# 5V.net
KiCad netlist of a schematic drawn in Altium Designer
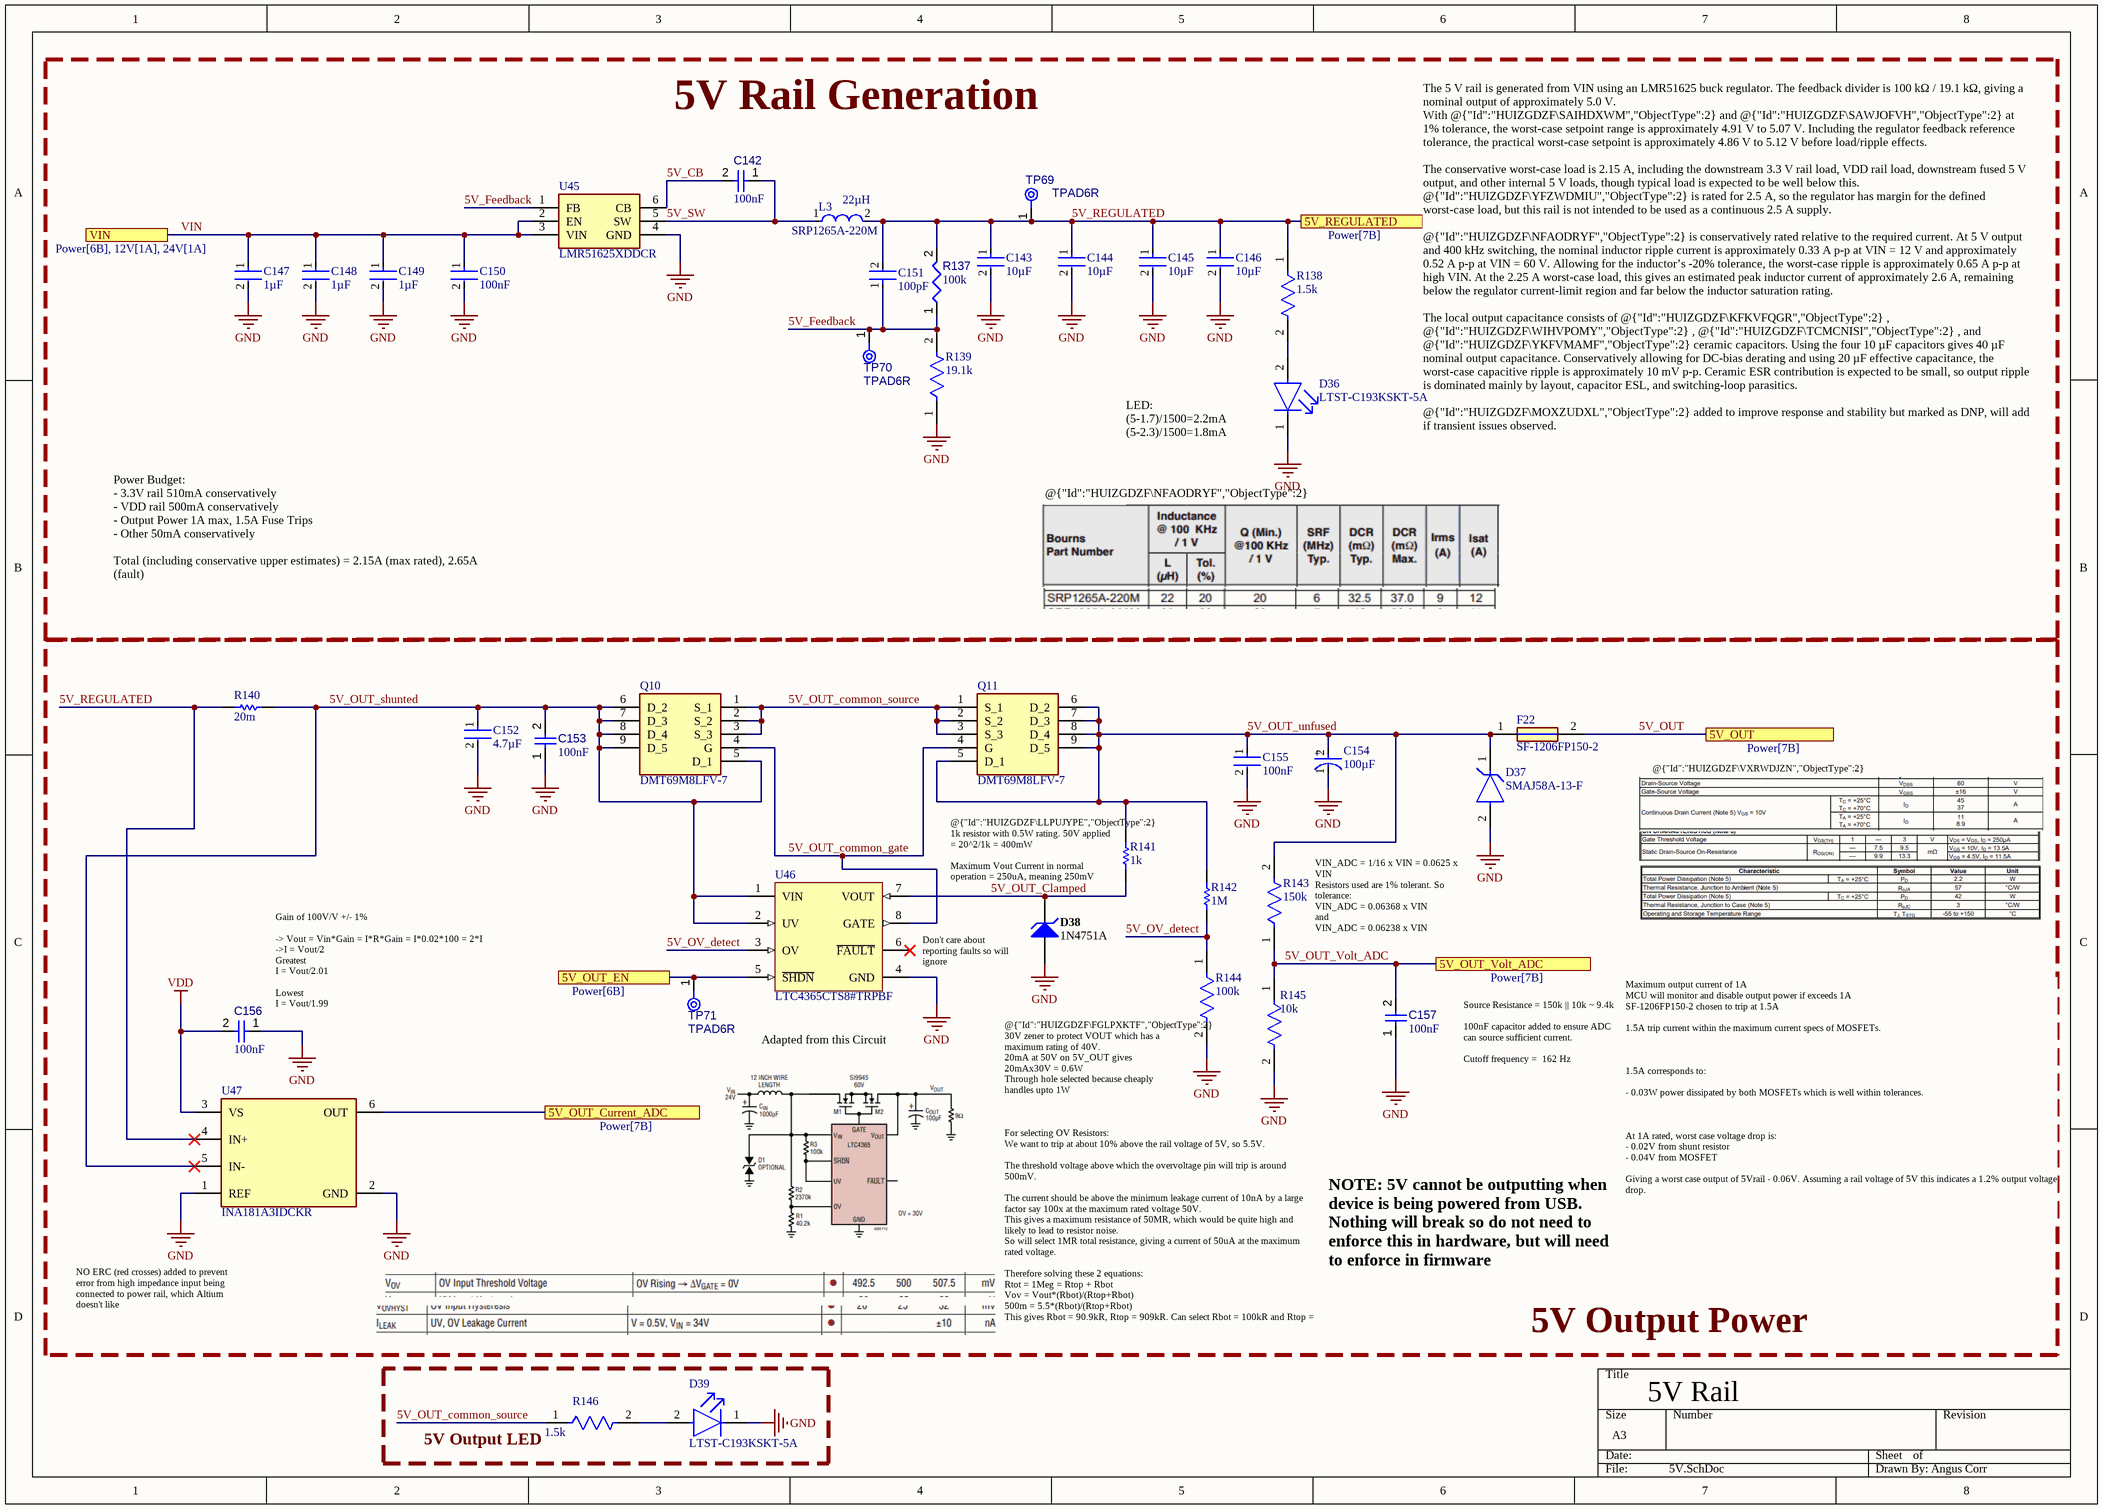
[diagram p0:  5V.SchDoc]

(export (version "E")
  (design (tool "Eeschema 10.0.6"))
  (components
    (comp (ref "C142")
      (value "100nF")
      (footprint "CAPC1608X90X40NL10T20")
      (description "Chip Capacitor, 100 nF, +/- 10%, 50 V, 0603 (1608 Metric)")
      (fields (field (name "TOLERANCE") "10%") (field (name "Comment") "Capacitor 100 nF +/-10% 50 V 0603"))
      (libsource (lib "HIL RIG FYP") (part "CAP-NP-2"))
    )
    (comp (ref "C143")
      (value "10µF")
      (footprint "FP-GRM31C-0_2-e0_3_0_8-IPC_C")
      (description "25V 10uF X7R ±10% 1206 Multilayer Ceramic Capacitors MLCC - SMD/SMT ROHS")
      (fields (field (name "TOLERANCE") "10%") (field (name "VOLTAGE") "25V"))
      (libsource (lib "HIL RIG FYP") (part "02cd4be3c70576c341d710602a673aa"))
    )
    (comp (ref "C144")
      (value "10µF")
      (footprint "FP-GRM31C-0_2-e0_3_0_8-IPC_C")
      (description "25V 10uF X7R ±10% 1206 Multilayer Ceramic Capacitors MLCC - SMD/SMT ROHS")
      (fields (field (name "TOLERANCE") "10%") (field (name "VOLTAGE") "25V"))
      (libsource (lib "HIL RIG FYP") (part "02cd4be3c70576c341d710602a673aa"))
    )
    (comp (ref "C145")
      (value "10µF")
      (footprint "FP-GRM31C-0_2-e0_3_0_8-IPC_C")
      (description "25V 10uF X7R ±10% 1206 Multilayer Ceramic Capacitors MLCC - SMD/SMT ROHS")
      (fields (field (name "TOLERANCE") "10%") (field (name "VOLTAGE") "25V"))
      (libsource (lib "HIL RIG FYP") (part "02cd4be3c70576c341d710602a673aa"))
    )
    (comp (ref "C146")
      (value "10µF")
      (footprint "FP-GRM31C-0_2-e0_3_0_8-IPC_C")
      (description "25V 10uF X7R ±10% 1206 Multilayer Ceramic Capacitors MLCC - SMD/SMT ROHS")
      (fields (field (name "TOLERANCE") "10%") (field (name "VOLTAGE") "25V"))
      (libsource (lib "HIL RIG FYP") (part "02cd4be3c70576c341d710602a673aa"))
    )
    (comp (ref "C147")
      (value "1µF")
      (footprint "FP-GRJ21B-0_35-MFG")
      (description "100V 1uF X7S ±10% 0805 Multilayer Ceramic Capacitors MLCC - SMD/SMT ROHS")
      (fields (field (name "TOLERANCE") "10%") (field (name "Comment") "GRJ21BC72A105KE11L"))
      (libsource (lib "HIL RIG FYP") (part "b4654b650e69147ec39a6b967a45e02"))
    )
    (comp (ref "C148")
      (value "1µF")
      (footprint "FP-GRJ21B-0_35-MFG")
      (description "100V 1uF X7S ±10% 0805 Multilayer Ceramic Capacitors MLCC - SMD/SMT ROHS")
      (fields (field (name "TOLERANCE") "10%") (field (name "Comment") "GRJ21BC72A105KE11L"))
      (libsource (lib "HIL RIG FYP") (part "b4654b650e69147ec39a6b967a45e02"))
    )
    (comp (ref "C149")
      (value "1µF")
      (footprint "FP-GRJ21B-0_35-MFG")
      (description "100V 1uF X7S ±10% 0805 Multilayer Ceramic Capacitors MLCC - SMD/SMT ROHS")
      (fields (field (name "TOLERANCE") "10%") (field (name "Comment") "GRJ21BC72A105KE11L"))
      (libsource (lib "HIL RIG FYP") (part "b4654b650e69147ec39a6b967a45e02"))
    )
    (comp (ref "C150")
      (value "100nF")
      (footprint "FP-GRM31C-0_2-e0_3_0_8-IPC_C")
      (description "100V 100nF C0G ±5% 1206 Multilayer Ceramic Capacitors MLCC - SMD/SMT ROHS")
      (fields (field (name "TOLERANCE") "5%") (field (name "Comment") "GRM31C5C2A104JA01L"))
      (libsource (lib "HIL RIG FYP") (part "02cd4be3c70576c341d710602a673aa"))
    )
    (comp (ref "C151")
      (value "100pF")
      (footprint "FP-C0603C-CF-IPC_B")
      (description "Multilayer Ceramic Capacitors MLCC - SMD/SMT 50V 100pF X8R 0603 1%")
      (fields (field (name "Comment") "C0603C101F5HACTU"))
      (libsource (lib "HIL RIG FYP") (part "b4654b650e69147ec39a6b967a45e02"))
    )
    (comp (ref "C152")
      (value "4.7µF")
      (footprint "FP-GRM21B-0_2-e0_2_0_7-MFG")
      (description "50V 4.7uF X7R ±10% 0805 Multilayer Ceramic Capacitors MLCC - SMD/SMT ROHS")
      (fields (field (name "TOLERANCE") "10%") (field (name "Comment") "GRM21BZ71H475KE15L"))
      (libsource (lib "HIL RIG FYP") (part "b4654b650e69147ec39a6b967a45e02"))
    )
    (comp (ref "C153")
      (value "100nF")
      (footprint "CAPC1608X90X40NL10T20")
      (description "Chip Capacitor, 100 nF, +/- 10%, 50 V, 0603 (1608 Metric)")
      (fields (field (name "TOLERANCE") "10%") (field (name "Comment") "Capacitor 100 nF +/-10% 50 V 0603"))
      (libsource (lib "HIL RIG FYP") (part "CAP-NP-2"))
    )
    (comp (ref "C154")
      (value "100µF")
      (footprint "FP-MVYAKE0-MFG")
      (description "Cap Aluminum 100uF 100V 20% (12.5 X 13.5mm) SMD 450mA 5000h 105°C T/R")
      (fields (field (name "TOLERANCE") "20%") (field (name "Comment") "EMVY101ARA101MKE0S"))
      (libsource (lib "HIL RIG FYP") (part "203bc49f2ac43e59fd269a8c329ed05"))
    )
    (comp (ref "C155")
      (value "100nF")
      (footprint "FP-GRM31C-0_2-e0_3_0_8-IPC_C")
      (description "100V 100nF C0G ±5% 1206 Multilayer Ceramic Capacitors MLCC - SMD/SMT ROHS")
      (fields (field (name "TOLERANCE") "5%") (field (name "Comment") "GRM31C5C2A104JA01L"))
      (libsource (lib "HIL RIG FYP") (part "02cd4be3c70576c341d710602a673aa"))
    )
    (comp (ref "C156")
      (value "100nF")
      (footprint "CAPC1608X90X40NL10T20")
      (description "Chip Capacitor, 100 nF, +/- 10%, 50 V, 0603 (1608 Metric)")
      (fields (field (name "TOLERANCE") "10%") (field (name "Comment") "Capacitor 100 nF +/-10% 50 V 0603"))
      (libsource (lib "HIL RIG FYP") (part "CAP-NP-2"))
    )
    (comp (ref "C157")
      (value "100nF")
      (footprint "CAPC1608X90X40NL10T20")
      (description "Chip Capacitor, 100 nF, +/- 10%, 50 V, 0603 (1608 Metric)")
      (fields (field (name "TOLERANCE") "10%") (field (name "Comment") "Capacitor 100 nF +/-10% 50 V 0603"))
      (libsource (lib "HIL RIG FYP") (part "CAP-NP-2"))
    )
    (comp (ref "D36")
      (value "LTST-C193KSKT-5A")
      (footprint "FP-LTST-C193KGKT-5A-MFG")
      (description "LED yellow 0603 wavelength 587~594.5nm light intensity 7.1~45mcd Front Mounting")
      (libsource (lib "HIL RIG FYP") (part "8706943c75ba83719d021d2fdc84c58"))
    )
    (comp (ref "D37")
      (value "SMAJ58A-13-F")
      (footprint "FP-SMA-MFG")
      (description "SMAJ Series 58 V 400 W SMT Uni-Directional TVS Diode - DO-214AC")
      (libsource (lib "HIL RIG FYP") (part "f813f71cba58e380607f5dd3caf9714"))
    )
    (comp (ref "D38")
      (value "1N4751A")
      (footprint "FAIR-DO-41-2_V")
      (description "1N4751 Series 1 W 30 V 5 uA Axial Through Hole Zener Diode - DO-41")
      (libsource (lib "HIL RIG FYP") (part "FAIR-DZEN-A1K2-2"))
    )
    (comp (ref "D39")
      (value "LTST-C193KSKT-5A")
      (footprint "FP-LTST-C193KGKT-5A-MFG")
      (description "LED yellow 0603 wavelength 587~594.5nm light intensity 7.1~45mcd Front Mounting")
      (libsource (lib "HIL RIG FYP") (part "8706943c75ba83719d021d2fdc84c58"))
    )
    (comp (ref "F22")
      (value "SF-1206FP150-2")
      (footprint "FUSC3116X70N")
      (description "Surface Mount Fuses 1.5A Fast Acting 1206 Singlfuse")
      (fields (field (name "MOUSER PART NUMBER") "652-SF-1206FP150-2"))
      (libsource (lib "HIL RIG FYP") (part "SF-1206FP150-2"))
    )
    (comp (ref "L3")
      (value "SRP1265A-220M")
      (footprint "FP-SRP1265A-MFG")
      (fields (field (name "TOLERANCE") "20%") (field (name "ALTIUM_VALUE") "22µH"))
      (libsource (lib "HIL RIG FYP") (part "725321dda6339637d4d059423bc1c3c"))
    )
    (comp (ref "Q10")
      (value "DMT69M8LFV-7")
      (footprint "DMP3036SFV7")
      (description "MOSFET MOSFET BVDSS: 41V-60V")
      (fields (field (name "MOUSER PART NUMBER") "621-DMT69M8LFV-7"))
      (libsource (lib "") (part "DMT69M8LFV-7_1"))
    )
    (comp (ref "Q11")
      (value "DMT69M8LFV-7")
      (footprint "DMP3036SFV7")
      (description "MOSFET MOSFET BVDSS: 41V-60V")
      (fields (field (name "MOUSER PART NUMBER") "621-DMT69M8LFV-7"))
      (libsource (lib "HIL RIG FYP") (part "DMT69M8LFV-7"))
    )
    (comp (ref "R137")
      (value "100k")
      (footprint "FP-AC0603-IPC_C")
      (description "Res Thick Film 0603 100K Ohm 1% 0.1W(1/10W) ±100ppm/C Pad SMD T/R Automotive")
      (fields (field (name "TOLERANCE") "1%") (field (name "Comment") "AC0603FR-07100KL"))
      (libsource (lib "HIL RIG FYP") (part "RES-2"))
    )
    (comp (ref "R138")
      (value "1.5k")
      (footprint "FP-RT0603-IPC_C")
      (description "Res Thin Film 0603 1.5K Ohm 0.1% 1/10W ±25ppm/°C Molded SMD SMD Paper T/R")
      (fields (field (name "TOLERANCE") "0.1%") (field (name "Comment") "RT0603BRD071K5L"))
      (libsource (lib "HIL RIG FYP") (part "1029c3af85768c4190bb7ad29bc67b5"))
    )
    (comp (ref "R139")
      (value "19.1k")
      (footprint "FP-RT0603-IPC_C")
      (description "100mW Thin Film Resistor ±25ppm/℃ ±0.1% 19.1kΩ 0603 Chip Resistor - Surface Mount ROHS")
      (fields (field (name "TOLERANCE") "0.1%") (field (name "Comment") "RT0603BRD0719K1L"))
      (libsource (lib "HIL RIG FYP") (part "1029c3af85768c4190bb7ad29bc67b5"))
    )
    (comp (ref "R140")
      (value "20m")
      (footprint "RESC3216X89X51NL25T25")
      (description "Res Metal Strip 1206 0.02 Ohm 1% 1/4W ±75ppm/°C Molded SMD SMD Embossed Plastic T/R")
      (fields (field (name "TOLERANCE") "1%") (field (name "Comment") "WSL1206R0200FEA"))
      (libsource (lib "HIL RIG FYP") (part "RES"))
    )
    (comp (ref "R141")
      (value "1k")
      (footprint "RESC3126X60X50ML10T20")
      (description "500mW Thick Film Resistors 200V ±100ppm/℃ ±1% 1kΩ 1210 Chip Resistor - Surface Mount ROHS")
      (fields (field (name "TOLERANCE") "1%") (field (name "Comment") "AC1210FR-071KL"))
      (libsource (lib "HIL RIG FYP") (part "RES"))
    )
    (comp (ref "R142")
      (value "1M")
      (footprint "RESC2013X60X35ML10T20")
      (fields (field (name "TOLERANCE") "0.1%") (field (name "Comment") "RT0805BRD071ML"))
      (libsource (lib "HIL RIG FYP") (part "RES"))
    )
    (comp (ref "R143")
      (value "150k")
      (footprint "FP-CRGCQ0603-IPC_A")
      (description "Res Thick Film 0603 150K Ohm 1% 0.1W(1/10W) ±100ppm/C Pad SMD Automotive T/R")
      (fields (field (name "TOLERANCE") "1%") (field (name "Comment") "CRGCQ0603F150K"))
      (libsource (lib "HIL RIG FYP") (part "1029c3af85768c4190bb7ad29bc67b5"))
    )
    (comp (ref "R144")
      (value "100k")
      (footprint "FP-RT0603-IPC_C")
      (description "100mW Thin Film Resistor 75V ±50ppm/℃ ±0.1% 100kΩ 0603 Chip Resistor - Surface Mount ROHS")
      (fields (field (name "TOLERANCE") "0.1%") (field (name "Comment") "RT0603BRE07100KL"))
      (libsource (lib "HIL RIG FYP") (part "1029c3af85768c4190bb7ad29bc67b5"))
    )
    (comp (ref "R145")
      (value "10k")
      (footprint "FP-RT0603-IPC_C")
      (description "Res Thin Film 0603 10K Ohm 0.1% 1/10W ¦25ppm/¦C SMD Paper T/R")
      (fields (field (name "TOLERANCE") "0.1%") (field (name "Comment") "RT0603BRD0710KL"))
      (libsource (lib "HIL RIG FYP") (part "1029c3af85768c4190bb7ad29bc67b5"))
    )
    (comp (ref "R146")
      (value "1.5k")
      (footprint "FP-RT0603-IPC_C")
      (description "Res Thin Film 0603 1.5K Ohm 0.1% 1/10W ±25ppm/°C Molded SMD SMD Paper T/R")
      (fields (field (name "TOLERANCE") "0.1%") (field (name "Comment") "RT0603BRD071K5L"))
      (libsource (lib "HIL RIG FYP") (part "1029c3af85768c4190bb7ad29bc67b5"))
    )
    (comp (ref "TP69")
      (value "TPAD6R")
      (footprint "TP06R")
      (description "0.6mm round")
      (libsource (lib "HIL RIG FYP") (part "CMP-001-0001-4"))
    )
    (comp (ref "TP70")
      (value "TPAD6R")
      (footprint "TP06R")
      (description "0.6mm round")
      (libsource (lib "HIL RIG FYP") (part "CMP-001-0001-4"))
    )
    (comp (ref "TP71")
      (value "TPAD6R")
      (footprint "TP06R")
      (description "0.6mm round")
      (libsource (lib "HIL RIG FYP") (part "CMP-001-0001-4"))
    )
    (comp (ref "U45")
      (value "LMR51625XDDCR")
      (footprint "SOT95P280X110-6N")
      (description "Switching Voltage Regulators SIMPLE SWITCHER synchronous buck converter with 4.3V-to-60V")
      (fields (field (name "MOUSER PART NUMBER") "595-LMR51625XDDCR"))
      (libsource (lib "HIL RIG FYP") (part "LMR51625XDDCR"))
    )
    (comp (ref "U46")
      (value "LTC4365CTS8#TRPBF")
      (footprint "LT-TS8-8-TSOT-23_V")
      (description "Overvoltage, Undervoltage and Reverse Supply Protection Controller")
      (libsource (lib "HIL RIG FYP") (part "LT-LTC4365-TS8-8"))
    )
    (comp (ref "U47")
      (value "INA181A3IDCKR")
      (footprint "FP-DCK0006A-IPC_A")
      (description "26-V bi-directional 350-kHz current-sense amplifier 6-SC70 -40 to 125")
      (libsource (lib "HIL RIG FYP") (part "a7b5cee9b6bc60f4871af0ee2c3b109"))
    )
  )
  (nets
    (net (code "1") (name "/5V_CB") (class "Default")
      (node (ref "C142") (pin "2") (pinfunction "2_2") (pintype "passive"))
      (node (ref "U45") (pin "6") (pinfunction "CB_6") (pintype "passive"))
    )
    (net (code "2") (name "/5V_Feedback") (class "Default")
      (node (ref "C151") (pin "1") (pinfunction "1_1") (pintype "passive"))
      (node (ref "R137") (pin "1") (pinfunction "1_1") (pintype "passive"))
      (node (ref "R139") (pin "2") (pinfunction "2_2") (pintype "passive"))
      (node (ref "TP70") (pin "1") (pinfunction "TP_1") (pintype "passive"))
      (node (ref "U45") (pin "1") (pinfunction "FB_1") (pintype "passive"))
    )
    (net (code "3") (name "/5V_OUT") (class "Default")
      (node (ref "F22") (pin "2") (pinfunction "2_2") (pintype "passive"))
    )
    (net (code "4") (name "/5V_OUT_Clamped") (class "Default")
      (node (ref "D38") (pin "2") (pinfunction "K_2") (pintype "passive"))
      (node (ref "R141") (pin "1") (pinfunction "1_1") (pintype "passive"))
      (node (ref "U46") (pin "7") (pinfunction "VOUT_7") (pintype "input"))
    )
    (net (code "5") (name "/5V_OUT_Current_ADC") (class "Default")
      (node (ref "U47") (pin "6") (pinfunction "OUT_6") (pintype "passive"))
    )
    (net (code "6") (name "/5V_OUT_EN") (class "Default")
      (node (ref "TP71") (pin "1") (pinfunction "TP_1") (pintype "passive"))
      (node (ref "U46") (pin "5") (pinfunction "~{SHDN}_5") (pintype "input"))
    )
    (net (code "7") (name "/5V_OUT_Volt_ADC") (class "Default")
      (node (ref "C157") (pin "2") (pinfunction "2_2") (pintype "passive"))
      (node (ref "R143") (pin "1") (pinfunction "1_1") (pintype "passive"))
      (node (ref "R145") (pin "1") (pinfunction "1_1") (pintype "passive"))
    )
    (net (code "8") (name "/5V_OUT_common_gate") (class "Default")
      (node (ref "Q10") (pin "4") (pinfunction "G_4") (pintype "passive"))
      (node (ref "Q11") (pin "4") (pinfunction "G_4") (pintype "passive"))
      (node (ref "U46") (pin "8") (pinfunction "GATE_8") (pintype "output"))
    )
    (net (code "9") (name "/5V_OUT_common_source") (class "Default")
      (node (ref "Q10") (pin "1") (pinfunction "S_1_1") (pintype "passive"))
      (node (ref "Q10") (pin "2") (pinfunction "S_2_2") (pintype "passive"))
      (node (ref "Q10") (pin "3") (pinfunction "S_3_3") (pintype "passive"))
      (node (ref "Q11") (pin "1") (pinfunction "S_1_1") (pintype "passive"))
      (node (ref "Q11") (pin "2") (pinfunction "S_2_2") (pintype "passive"))
      (node (ref "Q11") (pin "3") (pinfunction "S_3_3") (pintype "passive"))
      (node (ref "R146") (pin "1") (pinfunction "1_1") (pintype "passive"))
    )
    (net (code "10") (name "/5V_OUT_shunted") (class "Default")
      (node (ref "C152") (pin "1") (pinfunction "1_1") (pintype "passive"))
      (node (ref "C153") (pin "2") (pinfunction "2_2") (pintype "passive"))
      (node (ref "Q10") (pin "5") (pinfunction "D_1_5") (pintype "passive"))
      (node (ref "Q10") (pin "6") (pinfunction "D_2_6") (pintype "passive"))
      (node (ref "Q10") (pin "7") (pinfunction "D_3_7") (pintype "passive"))
      (node (ref "Q10") (pin "8") (pinfunction "D_4_8") (pintype "passive"))
      (node (ref "Q10") (pin "9") (pinfunction "D_5_9") (pintype "passive"))
      (node (ref "R140") (pin "2") (pinfunction "2_2") (pintype "passive"))
      (node (ref "U46") (pin "1") (pinfunction "VIN_1") (pintype "power_in"))
      (node (ref "U46") (pin "2") (pinfunction "UV_2") (pintype "input"))
      (node (ref "U47") (pin "5") (pinfunction "IN-_5") (pintype "tri_state"))
    )
    (net (code "11") (name "/5V_OUT_unfused") (class "Default")
      (node (ref "C154") (pin "2") (pinfunction "A_2") (pintype "passive"))
      (node (ref "C155") (pin "1") (pinfunction "1_1") (pintype "passive"))
      (node (ref "D37") (pin "1") (pinfunction "C_1") (pintype "passive"))
      (node (ref "F22") (pin "1") (pinfunction "1_1") (pintype "passive"))
      (node (ref "Q11") (pin "5") (pinfunction "D_1_5") (pintype "passive"))
      (node (ref "Q11") (pin "6") (pinfunction "D_2_6") (pintype "passive"))
      (node (ref "Q11") (pin "7") (pinfunction "D_3_7") (pintype "passive"))
      (node (ref "Q11") (pin "8") (pinfunction "D_4_8") (pintype "passive"))
      (node (ref "Q11") (pin "9") (pinfunction "D_5_9") (pintype "passive"))
      (node (ref "R141") (pin "2") (pinfunction "2_2") (pintype "passive"))
      (node (ref "R142") (pin "1") (pinfunction "1_1") (pintype "passive"))
      (node (ref "R143") (pin "2") (pinfunction "2_2") (pintype "passive"))
    )
    (net (code "12") (name "/5V_OV_detect") (class "Default")
      (node (ref "R142") (pin "2") (pinfunction "2_2") (pintype "passive"))
      (node (ref "R144") (pin "1") (pinfunction "1_1") (pintype "passive"))
      (node (ref "U46") (pin "3") (pinfunction "OV_3") (pintype "input"))
    )
    (net (code "13") (name "/5V_REGULATED") (class "Default")
      (node (ref "C143") (pin "1") (pinfunction "1_1") (pintype "passive"))
      (node (ref "C144") (pin "1") (pinfunction "1_1") (pintype "passive"))
      (node (ref "C145") (pin "1") (pinfunction "1_1") (pintype "passive"))
      (node (ref "C146") (pin "1") (pinfunction "1_1") (pintype "passive"))
      (node (ref "C151") (pin "2") (pinfunction "2_2") (pintype "passive"))
      (node (ref "L3") (pin "2") (pinfunction "2_2") (pintype "passive"))
      (node (ref "R137") (pin "2") (pinfunction "2_2") (pintype "passive"))
      (node (ref "R138") (pin "1") (pinfunction "1_1") (pintype "passive"))
      (node (ref "R140") (pin "1") (pinfunction "1_1") (pintype "passive"))
      (node (ref "TP69") (pin "1") (pinfunction "TP_1") (pintype "passive"))
      (node (ref "U47") (pin "4") (pinfunction "IN+_4") (pintype "tri_state"))
    )
    (net (code "14") (name "/5V_SW") (class "Default")
      (node (ref "C142") (pin "1") (pinfunction "1_1") (pintype "passive"))
      (node (ref "L3") (pin "1") (pinfunction "1_1") (pintype "passive"))
      (node (ref "U45") (pin "5") (pinfunction "SW_5") (pintype "passive"))
    )
    (net (code "15") (name "/VIN") (class "Default")
      (node (ref "C147") (pin "1") (pinfunction "1_1") (pintype "passive"))
      (node (ref "C148") (pin "1") (pinfunction "1_1") (pintype "passive"))
      (node (ref "C149") (pin "1") (pinfunction "1_1") (pintype "passive"))
      (node (ref "C150") (pin "1") (pinfunction "1_1") (pintype "passive"))
      (node (ref "U45") (pin "2") (pinfunction "EN_2") (pintype "passive"))
      (node (ref "U45") (pin "3") (pinfunction "VIN_3") (pintype "passive"))
    )
    (net (code "16") (name "GND") (class "Default")
      (node (ref "C143") (pin "2") (pinfunction "2_2") (pintype "passive"))
      (node (ref "C144") (pin "2") (pinfunction "2_2") (pintype "passive"))
      (node (ref "C145") (pin "2") (pinfunction "2_2") (pintype "passive"))
      (node (ref "C146") (pin "2") (pinfunction "2_2") (pintype "passive"))
      (node (ref "C147") (pin "2") (pinfunction "2_2") (pintype "passive"))
      (node (ref "C148") (pin "2") (pinfunction "2_2") (pintype "passive"))
      (node (ref "C149") (pin "2") (pinfunction "2_2") (pintype "passive"))
      (node (ref "C150") (pin "2") (pinfunction "2_2") (pintype "passive"))
      (node (ref "C152") (pin "2") (pinfunction "2_2") (pintype "passive"))
      (node (ref "C153") (pin "1") (pinfunction "1_1") (pintype "passive"))
      (node (ref "C154") (pin "1") (pinfunction "C_1") (pintype "passive"))
      (node (ref "C155") (pin "2") (pinfunction "2_2") (pintype "passive"))
      (node (ref "C156") (pin "1") (pinfunction "1_1") (pintype "passive"))
      (node (ref "C157") (pin "1") (pinfunction "1_1") (pintype "passive"))
      (node (ref "D36") (pin "1") (pinfunction "C_1") (pintype "passive"))
      (node (ref "D37") (pin "2") (pinfunction "A_2") (pintype "passive"))
      (node (ref "D38") (pin "1") (pinfunction "A_1") (pintype "passive"))
      (node (ref "D39") (pin "1") (pinfunction "C_1") (pintype "passive"))
      (node (ref "R139") (pin "1") (pinfunction "1_1") (pintype "passive"))
      (node (ref "R144") (pin "2") (pinfunction "2_2") (pintype "passive"))
      (node (ref "R145") (pin "2") (pinfunction "2_2") (pintype "passive"))
      (node (ref "U45") (pin "4") (pinfunction "GND_4") (pintype "passive"))
      (node (ref "U46") (pin "4") (pinfunction "GND_4") (pintype "power_in"))
      (node (ref "U47") (pin "1") (pinfunction "REF_1") (pintype "passive"))
      (node (ref "U47") (pin "2") (pinfunction "GND_2") (pintype "power_in"))
    )
    (net (code "17") (name "Net-(D36-A)") (class "Default")
      (node (ref "D36") (pin "2") (pinfunction "A_2") (pintype "passive"))
      (node (ref "R138") (pin "2") (pinfunction "2_2") (pintype "passive"))
    )
    (net (code "18") (name "Net-(D39-A)") (class "Default")
      (node (ref "D39") (pin "2") (pinfunction "A_2") (pintype "passive"))
      (node (ref "R146") (pin "2") (pinfunction "2_2") (pintype "passive"))
    )
    (net (code "19") (name "VDD") (class "Default")
      (node (ref "C156") (pin "2") (pinfunction "2_2") (pintype "passive"))
      (node (ref "U47") (pin "3") (pinfunction "VS_3") (pintype "power_in"))
    )
    (net (code "20") (name "unconnected-(U46-~{FAULT}-Pad6)") (class "Default")
      (node (ref "U46") (pin "6") (pinfunction "~{FAULT}_6") (pintype "open_collector+no_connect"))
    )
  )
)
